# xbowtie3.net
KiCad netlist of a schematic drawn in Altium Designer
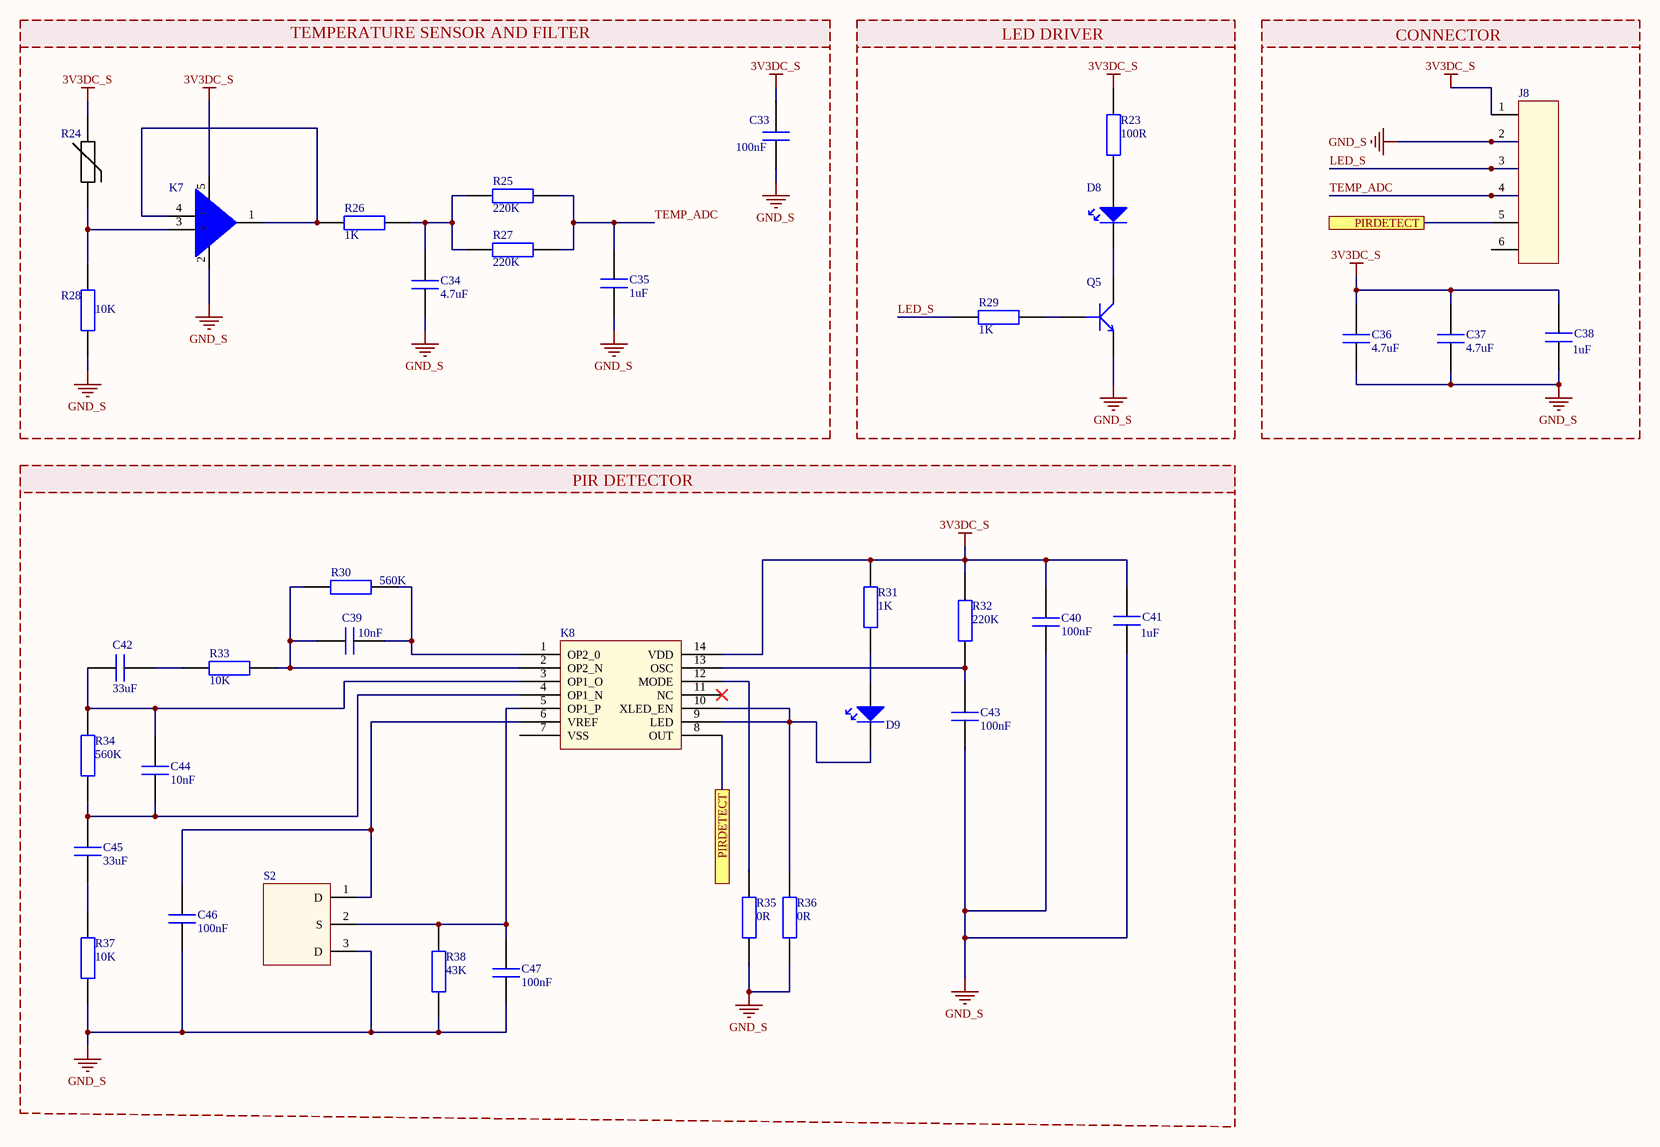
[diagram p0: xbowtie3.SchDoc]

(export (version "E")
  (design (tool "Eeschema 10.0.6"))
  (components
    (comp (ref "C33")
      (value "100nF")
      (footprint "CAP_CER 0805")
      (libsource (lib "xbowtie") (part "CAP CER 100nF 0805"))
    )
    (comp (ref "C34")
      (value "4.7uF")
      (footprint "CAP_CER 0805")
      (description "CAP CER 4.7uF 0805")
      (fields
        (field (name "MANUFACTURER") "Samsung")
        (field (name "MANUFACTURER PART NUMBER") "CL21A475KBQNNNE")
      )
      (libsource (lib "xbowtie") (part "CAP CER 4.7uF 0805"))
    )
    (comp (ref "C35")
      (value "CAP CER 1uF 0805")
      (footprint "CAP_CER 0805")
      (description "CAP CER 1uF %10 0805")
      (fields
        (field (name "MANUFACTURER") "Samsung")
        (field (name "MANUFACTURER PART NUMBER") "CL21B105KBFNNNE")
        (field (name "CAPACITANCE") "1uF")
      )
      (libsource (lib "xbowtie") (part "CAP CER 1uF 0805"))
    )
    (comp (ref "C36")
      (value "4.7uF")
      (footprint "CAP_CER 0805")
      (description "CAP CER 4.7uF 0805")
      (fields
        (field (name "MANUFACTURER") "Samsung")
        (field (name "MANUFACTURER PART NUMBER") "CL21A475KBQNNNE")
      )
      (libsource (lib "xbowtie") (part "CAP CER 4.7uF 0805"))
    )
    (comp (ref "C37")
      (value "4.7uF")
      (footprint "CAP_CER 0805")
      (description "CAP CER 4.7uF 0805")
      (fields
        (field (name "MANUFACTURER") "Samsung")
        (field (name "MANUFACTURER PART NUMBER") "CL21A475KBQNNNE")
      )
      (libsource (lib "xbowtie") (part "CAP CER 4.7uF 0805"))
    )
    (comp (ref "C38")
      (value "CAP CER 1uF 0805")
      (footprint "CAP_CER 0805")
      (description "CAP CER 1uF %10 0805")
      (fields
        (field (name "MANUFACTURER") "Samsung")
        (field (name "MANUFACTURER PART NUMBER") "CL21B105KBFNNNE")
        (field (name "CAPACITANCE") "1uF")
      )
      (libsource (lib "xbowtie") (part "CAP CER 1uF 0805"))
    )
    (comp (ref "C39")
      (value "10nF")
      (fields
        (field (name "MANUFACTURER") "Walsin Technologies")
        (field (name "MANUFACTURER PART NUMBER") "0603B103K160CT")
      )
      (libsource (lib "xbowtie") (part "CAP CER 10nF 0603"))
    )
    (comp (ref "C40")
      (value "CAP CER 100nF 0603")
      (description "Multilayer Ceramic Capacitor, 0.1 uF, 50 V, ± 10%, X7R, 0603 [1608 Metric]")
      (fields
        (field (name "MANUFACTURER") "KEMET")
        (field (name "MANUFACTURER PART NUMBER") "C0603C104K5RACTU")
        (field (name "CAPACITANCE") "100nF")
      )
      (libsource (lib "xbowtie") (part "CAP CER 100nF 0603"))
    )
    (comp (ref "C41")
      (value "CAP CER 1uF 0805")
      (footprint "CAP_CER 0805")
      (description "CAP CER 1uF %10 0805")
      (fields
        (field (name "MANUFACTURER") "Samsung")
        (field (name "MANUFACTURER PART NUMBER") "CL21B105KBFNNNE")
        (field (name "CAPACITANCE") "1uF")
      )
      (libsource (lib "xbowtie") (part "CAP CER 1uF 0805"))
    )
    (comp (ref "C42")
      (value "33uF")
      (footprint "CAP 1206")
      (libsource (lib "xbowtie") (part "CAP CER 33 uF 1206"))
    )
    (comp (ref "C43")
      (value "CAP CER 100nF 0603")
      (description "Multilayer Ceramic Capacitor, 0.1 uF, 50 V, ± 10%, X7R, 0603 [1608 Metric]")
      (fields
        (field (name "MANUFACTURER") "KEMET")
        (field (name "MANUFACTURER PART NUMBER") "C0603C104K5RACTU")
        (field (name "CAPACITANCE") "100nF")
      )
      (libsource (lib "xbowtie") (part "CAP CER 100nF 0603"))
    )
    (comp (ref "C44")
      (value "10nF")
      (fields
        (field (name "MANUFACTURER") "Walsin Technologies")
        (field (name "MANUFACTURER PART NUMBER") "0603B103K160CT")
      )
      (libsource (lib "xbowtie") (part "CAP CER 10nF 0603"))
    )
    (comp (ref "C45")
      (value "33uF")
      (footprint "CAP 1206")
      (libsource (lib "xbowtie") (part "CAP CER 33 uF 1206"))
    )
    (comp (ref "C46")
      (value "CAP CER 100nF 0603")
      (description "Multilayer Ceramic Capacitor, 0.1 uF, 50 V, ± 10%, X7R, 0603 [1608 Metric]")
      (fields
        (field (name "MANUFACTURER") "KEMET")
        (field (name "MANUFACTURER PART NUMBER") "C0603C104K5RACTU")
        (field (name "CAPACITANCE") "100nF")
      )
      (libsource (lib "xbowtie") (part "CAP CER 100nF 0603"))
    )
    (comp (ref "C47")
      (value "CAP CER 100nF 0603")
      (description "Multilayer Ceramic Capacitor, 0.1 uF, 50 V, ± 10%, X7R, 0603 [1608 Metric]")
      (fields
        (field (name "MANUFACTURER") "KEMET")
        (field (name "MANUFACTURER PART NUMBER") "C0603C104K5RACTU")
        (field (name "CAPACITANCE") "100nF")
      )
      (libsource (lib "xbowtie") (part "CAP CER 100nF 0603"))
    )
    (comp (ref "D8")
      (value "LED RED 0805")
      (footprint "LED 805")
      (libsource (lib "xbowtie") (part "LED RED 0805"))
    )
    (comp (ref "D9") (value "LED GREEN") (footprint "LED 805") (libsource (lib "xbowtie") (part "LED GREEN")))
    (comp (ref "J8")
      (value "64800611622")
      (footprint "64800611622")
      (description "1.50 mm, 6 pin connector")
      (fields (field (name "MANUFACTURER") "Wurth Electronics"))
      (libsource (lib "xbowtie") (part "64800611622_conn_6pin"))
    )
    (comp (ref "K7")
      (value "OPA314AIDBVR")
      (footprint "OPA314AIDBVR")
      (libsource (lib "xbowtie") (part "OPA314AIDBVR"))
    )
    (comp (ref "K8")
      (value "NCS36000DRG")
      (footprint "NCS36000DRG")
      (libsource (lib "xbowtie") (part "NCS36000DRG"))
    )
    (comp (ref "Q5")
      (value "MMBT3904-7-F")
      (footprint "MMBT3904-7-F")
      (description "Transistor General Purpose BJT NPN 40 Volt 0.2A Automotive 3-Pin SOT-23")
      (fields (field (name "MANUFACTURER") "Diodes Zetex"))
      (libsource (lib "xbowtie") (part "MMBT3904-7-F"))
    )
    (comp (ref "R23")
      (value "100R")
      (footprint "RES_0603")
      (libsource (lib "xbowtie") (part "RES 100 OHM 0603"))
    )
    (comp (ref "R24")
      (value "TFPT1206L1002FM")
      (footprint "TFPT1206L1002FM")
      (description "Thermistor PTC 10K Ohm 1% 2-Pin 1206 Surface Mount Solder Pad T/R Automotive")
      (fields (field (name "MANUFACTURER") "Vishay Dale") (field (name "TOLERANCE") "1%"))
      (libsource (lib "xbowtie") (part "TFPT1206L1002FM"))
    )
    (comp (ref "R25")
      (value "220K")
      (footprint "RES_0603")
      (libsource (lib "xbowtie") (part "RES 220K OHM 0603"))
    )
    (comp (ref "R26") (value "1K") (footprint "RES_0603") (libsource (lib "") (part "RES 1K OHM 0603_1")))
    (comp (ref "R27")
      (value "220K")
      (footprint "RES_0603")
      (libsource (lib "xbowtie") (part "RES 220K OHM 0603"))
    )
    (comp (ref "R28")
      (value "10K")
      (footprint "RES_0603")
      (description "Res Thin Film 0603 10K Ohm 0.1% 1/10W ±25ppm/°C Molded SMD SMD Punched Carrier T/R")
      (fields
        (field (name "MANUFACTURER") "Panasonic")
        (field (name "MANUFACTURER PART NUMBER") "ERA-3AEB103V")
      )
      (libsource (lib "xbowtie") (part "RES 10K OHM 0603"))
    )
    (comp (ref "R29") (value "1K") (footprint "RES_0603") (libsource (lib "") (part "RES 1K OHM 0603_1")))
    (comp (ref "R30")
      (value "560K")
      (footprint "RES_0603")
      (libsource (lib "xbowtie") (part "RES 560K OHM 0603"))
    )
    (comp (ref "R31")
      (value "1K")
      (footprint "RES_0603")
      (libsource (lib "xbowtie") (part "RES 1K OHM 0603"))
    )
    (comp (ref "R32") (value "220K") (footprint "RES_0603") (libsource (lib "") (part "RES 220K OHM 0603_1")))
    (comp (ref "R33")
      (value "10K")
      (footprint "RES_0603")
      (description "Res Thin Film 0603 10K Ohm 0.1% 1/10W ±25ppm/°C Molded SMD SMD Punched Carrier T/R")
      (fields
        (field (name "MANUFACTURER") "Panasonic")
        (field (name "MANUFACTURER PART NUMBER") "ERA-3AEB103V")
      )
      (libsource (lib "") (part "RES 10K OHM 0603_2"))
    )
    (comp (ref "R34") (value "560K") (footprint "RES_0603") (libsource (lib "") (part "RES 560K OHM 0603_1")))
    (comp (ref "R35")
      (value "0R")
      (footprint "RES_0603")
      (description "Zero Ohm Resistor, Jumper, 0603 [1608 Metric], Thick Film, 100 mW, 1 A, Surface Mount")
      (fields
        (field (name "MANUFACTURER") "Yageo")
        (field (name "MANUFACTURER PART NUMBER") "RC0603JR-070RL")
      )
      (libsource (lib "xbowtie") (part "RES 0 OHM 0603"))
    )
    (comp (ref "R36")
      (value "0R")
      (footprint "RES_0603")
      (description "Zero Ohm Resistor, Jumper, 0603 [1608 Metric], Thick Film, 100 mW, 1 A, Surface Mount")
      (fields
        (field (name "MANUFACTURER") "Yageo")
        (field (name "MANUFACTURER PART NUMBER") "RC0603JR-070RL")
      )
      (libsource (lib "xbowtie") (part "RES 0 OHM 0603"))
    )
    (comp (ref "R37")
      (value "10K")
      (footprint "RES_0603")
      (description "Res Thin Film 0603 10K Ohm 0.1% 1/10W ±25ppm/°C Molded SMD SMD Punched Carrier T/R")
      (fields
        (field (name "MANUFACTURER") "Panasonic")
        (field (name "MANUFACTURER PART NUMBER") "ERA-3AEB103V")
      )
      (libsource (lib "") (part "RES 10K OHM 0603_1"))
    )
    (comp (ref "R38")
      (value "43K")
      (footprint "RES_0603")
      (libsource (lib "xbowtie") (part "RES 43K OHM 0603"))
    )
    (comp (ref "S2")
      (value "LHI 878/3902")
      (footprint "LHI 878")
      (description "Sensor Pyro Detector Dual Motion")
      (fields
        (field (name "MANUFACTURER") "Excelitas")
        (field (name "MANUFACTURER PART NUMBER") "LHI878/3902")
      )
      (libsource (lib "xbowtie") (part "LHI 878/3902"))
    )
  )
  (nets
    (net (code "1") (name "/LED_S") (class "Default")
      (node (ref "J8") (pin "3") (pinfunction "TX_3") (pintype "passive"))
      (node (ref "R29") (pin "1") (pinfunction "1_1") (pintype "passive"))
    )
    (net (code "2") (name "/PIRDETECT") (class "Default")
      (node (ref "J8") (pin "5") (pinfunction "GND_5") (pintype "passive"))
      (node (ref "K8") (pin "8") (pinfunction "OUT_8") (pintype "passive"))
    )
    (net (code "3") (name "/TEMP_ADC") (class "Default")
      (node (ref "C35") (pin "2") (pinfunction "2_2") (pintype "passive"))
      (node (ref "J8") (pin "4") (pinfunction "NC_4") (pintype "passive"))
      (node (ref "R25") (pin "2") (pinfunction "2_2") (pintype "passive"))
      (node (ref "R27") (pin "2") (pinfunction "2_2") (pintype "passive"))
    )
    (net (code "4") (name "3V3DC_S") (class "Default")
      (node (ref "C33") (pin "2") (pinfunction "2_2") (pintype "passive"))
      (node (ref "C36") (pin "2") (pinfunction "2_2") (pintype "passive"))
      (node (ref "C37") (pin "2") (pinfunction "2_2") (pintype "passive"))
      (node (ref "C38") (pin "2") (pinfunction "2_2") (pintype "passive"))
      (node (ref "C40") (pin "2") (pinfunction "2_2") (pintype "passive"))
      (node (ref "C41") (pin "2") (pinfunction "2_2") (pintype "passive"))
      (node (ref "J8") (pin "1") (pinfunction "VCC_1") (pintype "passive"))
      (node (ref "K7") (pin "5") (pinfunction "V+_5") (pintype "power_in"))
      (node (ref "K8") (pin "14") (pinfunction "VDD_14") (pintype "passive"))
      (node (ref "R23") (pin "2") (pinfunction "2_2") (pintype "passive"))
      (node (ref "R24") (pin "2") (pinfunction "0_2") (pintype "passive"))
      (node (ref "R31") (pin "2") (pinfunction "2_2") (pintype "passive"))
      (node (ref "R32") (pin "2") (pinfunction "2_2") (pintype "passive"))
    )
    (net (code "5") (name "GND_S") (class "Default")
      (node (ref "C33") (pin "1") (pinfunction "1_1") (pintype "passive"))
      (node (ref "C34") (pin "1") (pinfunction "1_1") (pintype "passive"))
      (node (ref "C35") (pin "1") (pinfunction "1_1") (pintype "passive"))
      (node (ref "C36") (pin "1") (pinfunction "1_1") (pintype "passive"))
      (node (ref "C37") (pin "1") (pinfunction "1_1") (pintype "passive"))
      (node (ref "C38") (pin "1") (pinfunction "1_1") (pintype "passive"))
      (node (ref "C40") (pin "1") (pinfunction "1_1") (pintype "passive"))
      (node (ref "C41") (pin "1") (pinfunction "1_1") (pintype "passive"))
      (node (ref "C43") (pin "1") (pinfunction "1_1") (pintype "passive"))
      (node (ref "C46") (pin "1") (pinfunction "1_1") (pintype "passive"))
      (node (ref "C47") (pin "1") (pinfunction "1_1") (pintype "passive"))
      (node (ref "J8") (pin "2") (pinfunction "RX_2") (pintype "passive"))
      (node (ref "K7") (pin "2") (pinfunction "V-_2") (pintype "power_in"))
      (node (ref "Q5") (pin "2") (pinfunction "E_2") (pintype "passive"))
      (node (ref "R28") (pin "2") (pinfunction "2_2") (pintype "passive"))
      (node (ref "R35") (pin "1") (pinfunction "1_1") (pintype "passive"))
      (node (ref "R36") (pin "1") (pinfunction "1_1") (pintype "passive"))
      (node (ref "R37") (pin "1") (pinfunction "1_1") (pintype "passive"))
      (node (ref "R38") (pin "1") (pinfunction "1_1") (pintype "passive"))
      (node (ref "S2") (pin "3") (pinfunction "D_3") (pintype "passive"))
    )
    (net (code "6") (name "Net-(C34-Pad2)") (class "Default")
      (node (ref "C34") (pin "2") (pinfunction "2_2") (pintype "passive"))
      (node (ref "R25") (pin "1") (pinfunction "1_1") (pintype "passive"))
      (node (ref "R26") (pin "2") (pinfunction "2_2") (pintype "passive"))
      (node (ref "R27") (pin "1") (pinfunction "1_1") (pintype "passive"))
    )
    (net (code "7") (name "Net-(C42-Pad2)") (class "Default")
      (node (ref "C42") (pin "2") (pinfunction "2_2") (pintype "passive"))
      (node (ref "R33") (pin "1") (pinfunction "1_1") (pintype "passive"))
    )
    (net (code "8") (name "Net-(C45-Pad1)") (class "Default")
      (node (ref "C45") (pin "1") (pinfunction "1_1") (pintype "passive"))
      (node (ref "R37") (pin "2") (pinfunction "2_2") (pintype "passive"))
    )
    (net (code "9") (name "Net-(D8-Pad1)") (class "Default")
      (node (ref "D8") (pin "1") (pinfunction "1_1") (pintype "passive"))
      (node (ref "Q5") (pin "C") (pinfunction "C_C") (pintype "passive"))
    )
    (net (code "10") (name "Net-(D8-Pad2)") (class "Default")
      (node (ref "D8") (pin "2") (pinfunction "2_2") (pintype "passive"))
      (node (ref "R23") (pin "1") (pinfunction "1_1") (pintype "passive"))
    )
    (net (code "11") (name "Net-(D9-Pad2)") (class "Default")
      (node (ref "D9") (pin "2") (pinfunction "2_2") (pintype "passive"))
      (node (ref "R31") (pin "1") (pinfunction "1_1") (pintype "passive"))
    )
    (net (code "12") (name "Net-(K7-+)") (class "Default")
      (node (ref "K7") (pin "3") (pinfunction "+_3") (pintype "power_in"))
      (node (ref "R24") (pin "1") (pinfunction "1_1") (pintype "passive"))
      (node (ref "R28") (pin "1") (pinfunction "1_1") (pintype "passive"))
    )
    (net (code "13") (name "Net-(K7--)") (class "Default")
      (node (ref "K7") (pin "1") (pinfunction "OUT_1") (pintype "power_in"))
      (node (ref "K7") (pin "4") (pinfunction "-_4") (pintype "power_in"))
      (node (ref "R26") (pin "1") (pinfunction "1_1") (pintype "passive"))
    )
    (net (code "14") (name "Net-(K8-LED)") (class "Default")
      (node (ref "D9") (pin "1") (pinfunction "1_1") (pintype "passive"))
      (node (ref "K8") (pin "10") (pinfunction "XLED_EN_10") (pintype "passive"))
      (node (ref "K8") (pin "9") (pinfunction "LED_9") (pintype "passive"))
      (node (ref "R36") (pin "2") (pinfunction "2_2") (pintype "passive"))
    )
    (net (code "15") (name "Net-(K8-MODE)") (class "Default")
      (node (ref "K8") (pin "12") (pinfunction "MODE_12") (pintype "passive"))
      (node (ref "R35") (pin "2") (pinfunction "2_2") (pintype "passive"))
    )
    (net (code "16") (name "Net-(K8-OP1_N)") (class "Default")
      (node (ref "C44") (pin "1") (pinfunction "1_1") (pintype "passive"))
      (node (ref "C45") (pin "2") (pinfunction "2_2") (pintype "passive"))
      (node (ref "K8") (pin "4") (pinfunction "OP1_N_4") (pintype "passive"))
      (node (ref "R34") (pin "1") (pinfunction "1_1") (pintype "passive"))
    )
    (net (code "17") (name "Net-(K8-OP1_O)") (class "Default")
      (node (ref "C42") (pin "1") (pinfunction "1_1") (pintype "passive"))
      (node (ref "C44") (pin "2") (pinfunction "2_2") (pintype "passive"))
      (node (ref "K8") (pin "3") (pinfunction "OP1_O_3") (pintype "passive"))
      (node (ref "R34") (pin "2") (pinfunction "2_2") (pintype "passive"))
    )
    (net (code "18") (name "Net-(K8-OP1_P)") (class "Default")
      (node (ref "C47") (pin "2") (pinfunction "2_2") (pintype "passive"))
      (node (ref "K8") (pin "5") (pinfunction "OP1_P_5") (pintype "passive"))
      (node (ref "R38") (pin "2") (pinfunction "2_2") (pintype "passive"))
      (node (ref "S2") (pin "2") (pinfunction "S_2") (pintype "passive"))
    )
    (net (code "19") (name "Net-(K8-OP2_0)") (class "Default")
      (node (ref "C39") (pin "2") (pinfunction "2_2") (pintype "passive"))
      (node (ref "K8") (pin "1") (pinfunction "OP2_0_1") (pintype "passive"))
      (node (ref "R30") (pin "2") (pinfunction "2_2") (pintype "passive"))
    )
    (net (code "20") (name "Net-(K8-OP2_N)") (class "Default")
      (node (ref "C39") (pin "1") (pinfunction "1_1") (pintype "passive"))
      (node (ref "K8") (pin "2") (pinfunction "OP2_N_2") (pintype "passive"))
      (node (ref "R30") (pin "1") (pinfunction "1_1") (pintype "passive"))
      (node (ref "R33") (pin "2") (pinfunction "2_2") (pintype "passive"))
    )
    (net (code "21") (name "Net-(K8-OSC)") (class "Default")
      (node (ref "C43") (pin "2") (pinfunction "2_2") (pintype "passive"))
      (node (ref "K8") (pin "13") (pinfunction "OSC_13") (pintype "passive"))
      (node (ref "R32") (pin "1") (pinfunction "1_1") (pintype "passive"))
    )
    (net (code "22") (name "Net-(K8-VREF)") (class "Default")
      (node (ref "C46") (pin "2") (pinfunction "2_2") (pintype "passive"))
      (node (ref "K8") (pin "6") (pinfunction "VREF_6") (pintype "passive"))
      (node (ref "S2") (pin "1") (pinfunction "D_1") (pintype "passive"))
    )
    (net (code "23") (name "Net-(Q5-B)") (class "Default")
      (node (ref "Q5") (pin "1") (pinfunction "B_1") (pintype "passive"))
      (node (ref "R29") (pin "2") (pinfunction "2_2") (pintype "passive"))
    )
    (net (code "24") (name "unconnected-(J8-GND-Pad6)") (class "Default")
      (node (ref "J8") (pin "6") (pinfunction "GND_6") (pintype "passive"))
    )
    (net (code "25") (name "unconnected-(K8-NC-Pad11)") (class "Default")
      (node (ref "K8") (pin "11") (pinfunction "NC_11") (pintype "passive+no_connect"))
    )
    (net (code "26") (name "unconnected-(K8-VSS-Pad7)") (class "Default")
      (node (ref "K8") (pin "7") (pinfunction "VSS_7") (pintype "passive"))
    )
  )
)
